# Puzzle_Light_Sensor_v1_2.net
KiCad netlist of a schematic drawn in EAGLE
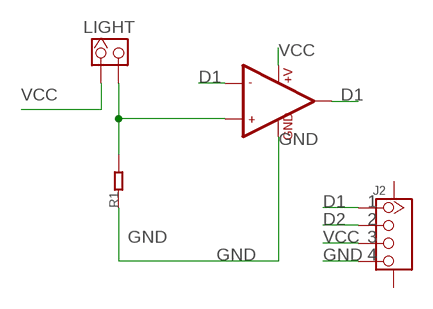
[diagram p0: schematic, sheet 1]

(export (version "E")
  (design (tool "Eeschema 10.0.6"))
  (components
    (comp (ref "J2")
      (value "TWIG-4P-2.0-SMD-FEMALE-REINFORCE'DD'")
      (footprint "eagle-import:4P-SMD-2.0")
      (libsource (lib "eagle-import") (part "TWIG-4P-2.0-SMD-FEMALE-REINFORCE'DD'"))
    )
    (comp (ref "LIGHT")
      (value "HEADER_1X2_2.54")
      (footprint "eagle-import:CK_1_2")
      (libsource (lib "eagle-import") (part "HEADER_1X2_2.54"))
    )
    (comp (ref "R1")
      (value "R0603")
      (footprint "eagle-import:0603")
      (libsource (lib "eagle-import") (part "R0603"))
    )
    (comp (ref "U1")
      (value "LMV358")
      (footprint "eagle-import:SO08")
      (libsource (lib "eagle-import") (part "LMV358"))
    )
  )
  (nets
    (net (code "1") (name "/D1") (class "Default")
      (node (ref "J2") (pin "1") (pinfunction "1_1") (pintype "bidirectional"))
      (node (ref "U1") (pin "1") (pinfunction "OUT1_1") (pintype "output"))
      (node (ref "U1") (pin "2") (pinfunction "-IN1_2") (pintype "input"))
    )
    (net (code "2") (name "/D2") (class "Default")
      (node (ref "J2") (pin "2") (pinfunction "2_2") (pintype "bidirectional"))
    )
    (net (code "3") (name "/GND") (class "Default")
      (node (ref "J2") (pin "4") (pinfunction "4_4") (pintype "bidirectional"))
      (node (ref "R1") (pin "1") (pinfunction "1_1") (pintype "bidirectional"))
      (node (ref "U1") (pin "4") (pinfunction "GND_4") (pintype "power_in"))
    )
    (net (code "4") (name "/VCC") (class "Default")
      (node (ref "J2") (pin "3") (pinfunction "3_3") (pintype "bidirectional"))
      (node (ref "LIGHT") (pin "1") (pinfunction "1_1") (pintype "bidirectional"))
      (node (ref "U1") (pin "8") (pinfunction "+V_8") (pintype "power_in"))
    )
    (net (code "5") (name "Net-(U1A-+IN1)") (class "Default")
      (node (ref "LIGHT") (pin "2") (pinfunction "2_2") (pintype "bidirectional"))
      (node (ref "R1") (pin "2") (pinfunction "2_2") (pintype "bidirectional"))
      (node (ref "U1") (pin "3") (pinfunction "+IN1_3") (pintype "input"))
    )
    (net (code "6") (name "unconnected-(J2-PadSS1)") (class "Default")
      (node (ref "J2") (pin "SS1") (pinfunction "SS1_SS1") (pintype "bidirectional"))
    )
    (net (code "7") (name "unconnected-(J2-PadSS2)") (class "Default")
      (node (ref "J2") (pin "SS2") (pinfunction "SS2_SS2") (pintype "bidirectional"))
    )
  )
)
